# 3.net
KiCad netlist of a schematic drawn in Altium Designer
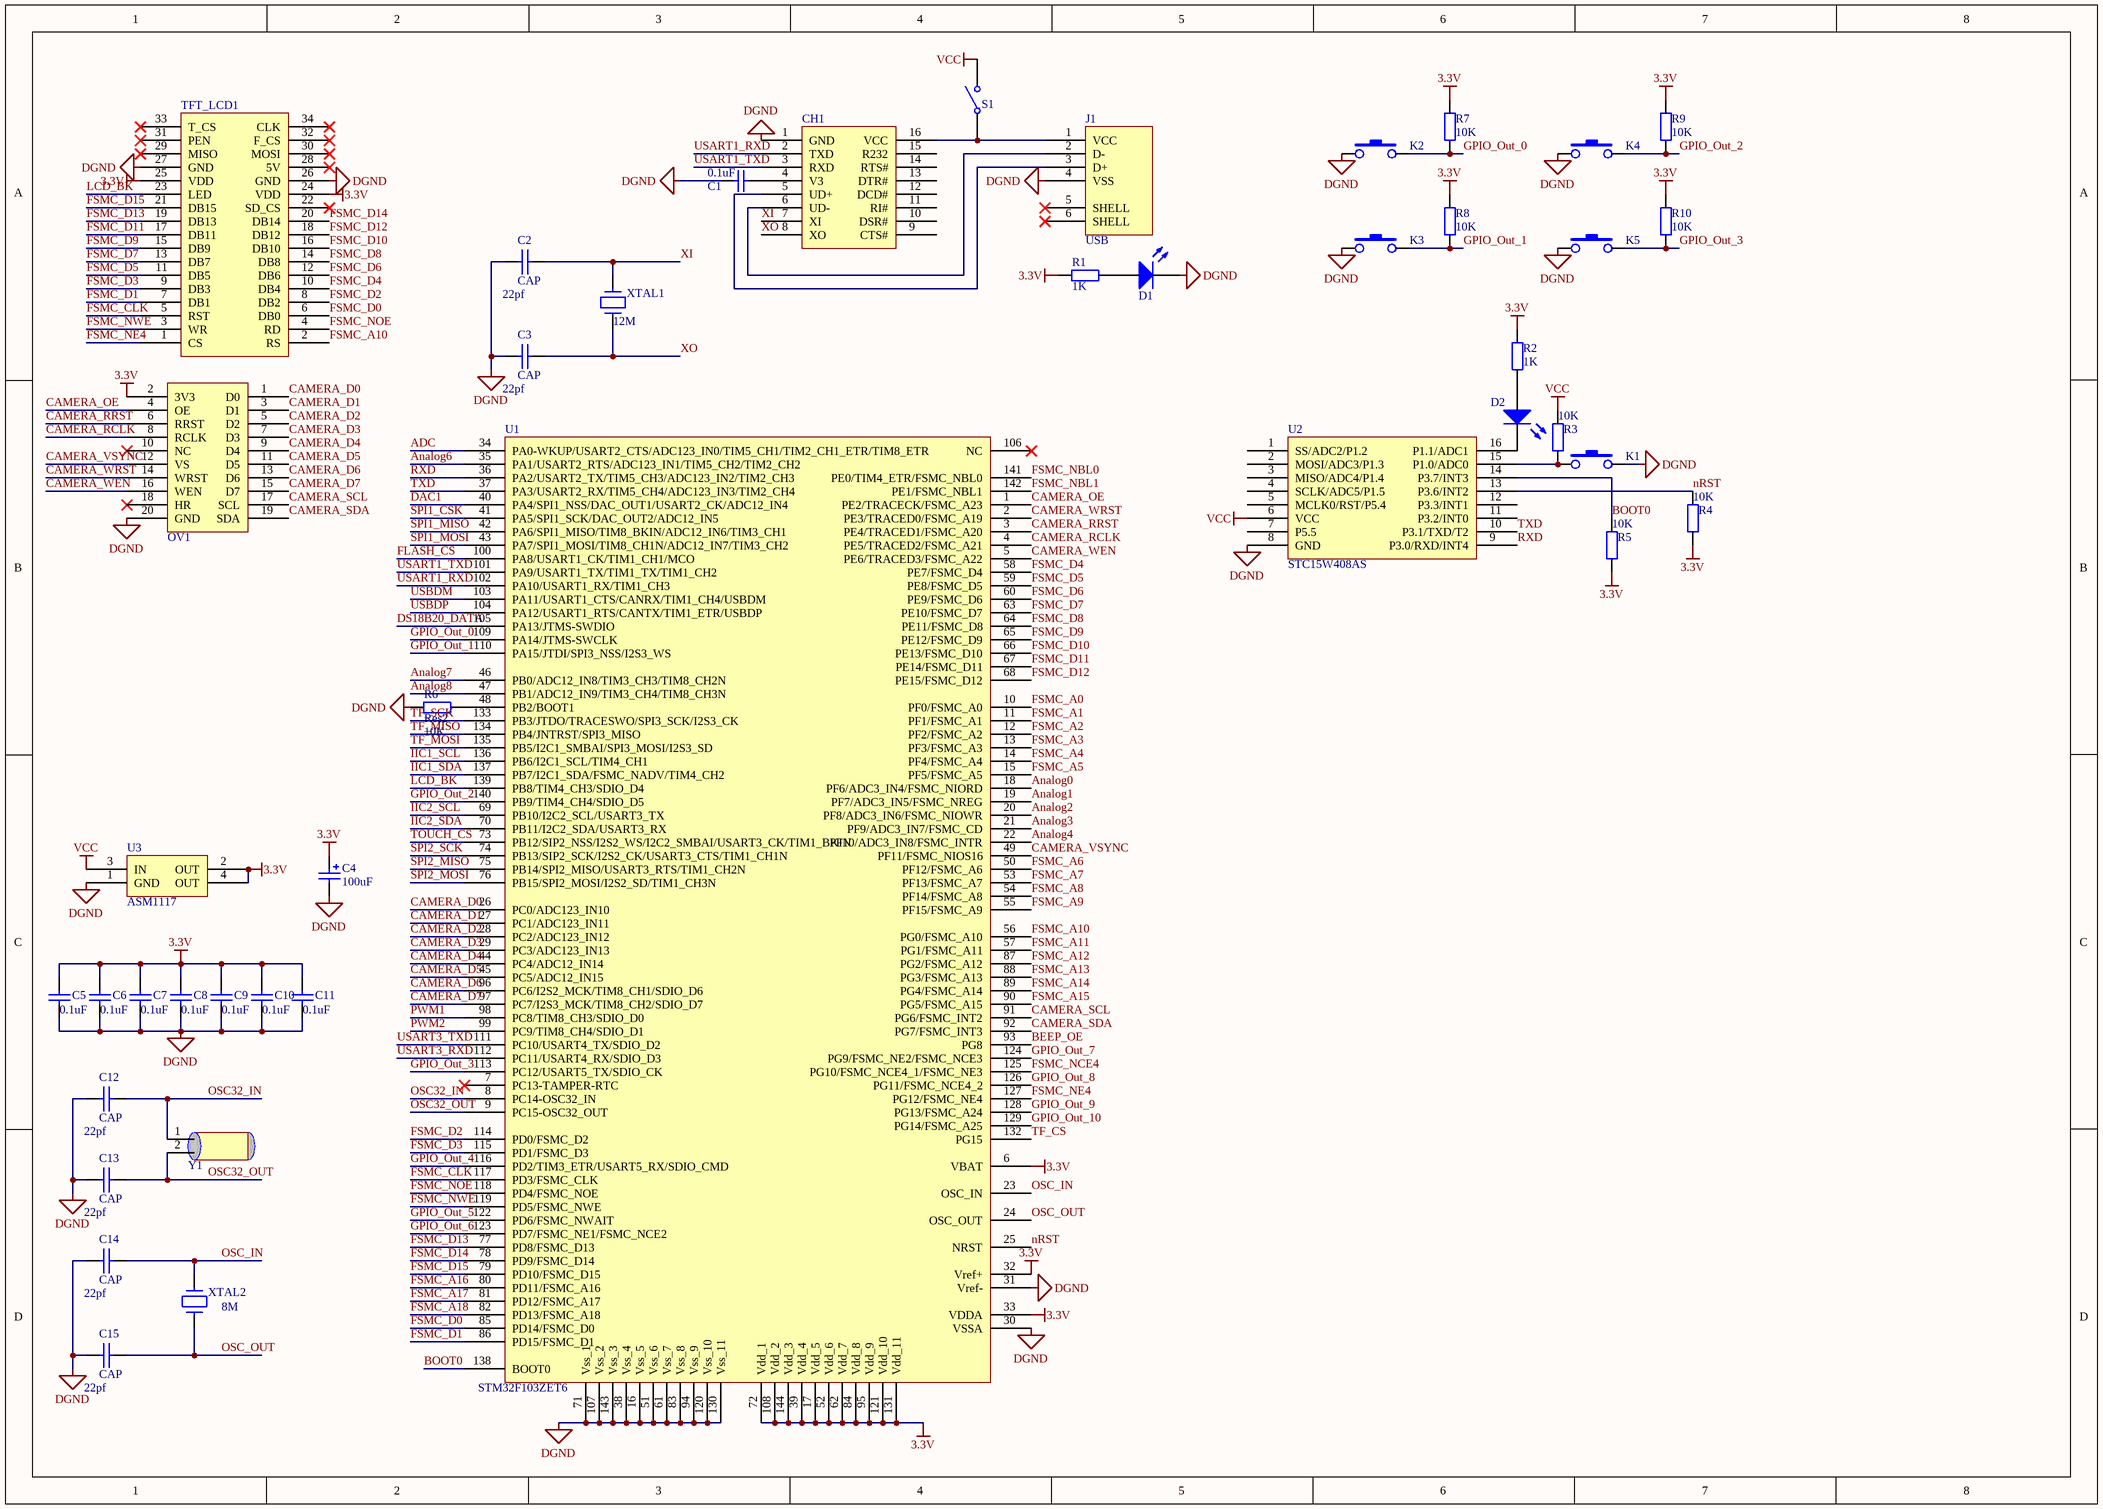
[diagram p0: 测试板3.SchDoc]

(export (version "E")
  (design (tool "Eeschema 10.0.6"))
  (components
    (comp (ref "C1")
      (value "0.1uF")
      (footprint "0805")
      (description "Capacitor")
      (fields (field (name "Comment") "Cap") (field (name "PUBLISHER") "Altium Limited"))
      (libsource (lib "Miscellaneous Devices") (part "Cap"))
    )
    (comp (ref "C2")
      (value "CAP")
      (footprint "0805")
      (fields (field (name "ALTIUM_VALUE") "22pf"))
      (libsource (lib "常用元件库") (part "CAP"))
    )
    (comp (ref "C3")
      (value "CAP")
      (footprint "0805")
      (fields (field (name "ALTIUM_VALUE") "22pf"))
      (libsource (lib "常用元件库") (part "CAP"))
    )
    (comp (ref "C4")
      (value "100uF")
      (footprint "RB.1/.3")
      (description "Polarized Capacitor (Axial)")
      (fields (field (name "Comment") "Cap Pol2") (field (name "PUBLISHER") "Altium Limited"))
      (libsource (lib "Miscellaneous Devices") (part "Cap Pol2"))
    )
    (comp (ref "C5")
      (value "0.1uF")
      (footprint "0805")
      (description "Capacitor")
      (fields (field (name "Comment") "Cap") (field (name "PUBLISHER") "Altium Limited"))
      (libsource (lib "Miscellaneous Devices") (part "Cap"))
    )
    (comp (ref "C6")
      (value "0.1uF")
      (footprint "0805")
      (description "Capacitor")
      (fields (field (name "Comment") "Cap") (field (name "PUBLISHER") "Altium Limited"))
      (libsource (lib "Miscellaneous Devices") (part "Cap"))
    )
    (comp (ref "C7")
      (value "0.1uF")
      (footprint "0805")
      (description "Capacitor")
      (fields (field (name "Comment") "Cap") (field (name "PUBLISHER") "Altium Limited"))
      (libsource (lib "Miscellaneous Devices") (part "Cap"))
    )
    (comp (ref "C8")
      (value "0.1uF")
      (footprint "0805")
      (description "Capacitor")
      (fields (field (name "Comment") "Cap") (field (name "PUBLISHER") "Altium Limited"))
      (libsource (lib "Miscellaneous Devices") (part "Cap"))
    )
    (comp (ref "C9")
      (value "0.1uF")
      (footprint "0805")
      (description "Capacitor")
      (fields (field (name "Comment") "Cap") (field (name "PUBLISHER") "Altium Limited"))
      (libsource (lib "Miscellaneous Devices") (part "Cap"))
    )
    (comp (ref "C10")
      (value "0.1uF")
      (footprint "0805")
      (description "Capacitor")
      (fields (field (name "Comment") "Cap") (field (name "PUBLISHER") "Altium Limited"))
      (libsource (lib "Miscellaneous Devices") (part "Cap"))
    )
    (comp (ref "C11")
      (value "0.1uF")
      (footprint "0805")
      (description "Capacitor")
      (fields (field (name "Comment") "Cap") (field (name "PUBLISHER") "Altium Limited"))
      (libsource (lib "Miscellaneous Devices") (part "Cap"))
    )
    (comp (ref "C12")
      (value "CAP")
      (footprint "0805")
      (fields (field (name "ALTIUM_VALUE") "22pf"))
      (libsource (lib "常用元件库") (part "CAP"))
    )
    (comp (ref "C13")
      (value "CAP")
      (footprint "0805")
      (fields (field (name "ALTIUM_VALUE") "22pf"))
      (libsource (lib "常用元件库") (part "CAP"))
    )
    (comp (ref "C14")
      (value "CAP")
      (footprint "0805")
      (fields (field (name "ALTIUM_VALUE") "22pf"))
      (libsource (lib "常用元件库") (part "CAP"))
    )
    (comp (ref "C15")
      (value "CAP")
      (footprint "0805")
      (fields (field (name "ALTIUM_VALUE") "22pf"))
      (libsource (lib "常用元件库") (part "CAP"))
    )
    (comp (ref "CH1")
      (value "Component_1")
      (footprint "SOIC127P600X170-16N")
      (libsource (lib "CH340G") (part "Component_1"))
    )
    (comp (ref "D1")
      (value "LED0")
      (footprint "LED-0805")
      (description "发光二极管")
      (fields (field (name "PUBLISHER") "Altium Limited"))
      (libsource (lib "fszhang") (part "LED0"))
    )
    (comp (ref "D2")
      (value "LED0")
      (footprint "LED-0805")
      (description "发光二极管")
      (fields (field (name "PUBLISHER") "Altium Limited"))
      (libsource (lib "fszhang") (part "LED0"))
    )
    (comp (ref "J1")
      (value "USB")
      (footprint "USB_B1")
      (description "USB接口")
      (libsource (lib "HDR_fszhang") (part "USB"))
    )
    (comp (ref "K1") (value "button") (footprint "SW_PB4_A1") (libsource (lib "my Library") (part "button")))
    (comp (ref "K2") (value "button") (footprint "SW_PB4_A1") (libsource (lib "my Library") (part "button")))
    (comp (ref "K3") (value "button") (footprint "SW_PB4_A1") (libsource (lib "my Library") (part "button")))
    (comp (ref "K4") (value "button") (footprint "SW_PB4_A1") (libsource (lib "my Library") (part "button")))
    (comp (ref "K5") (value "button") (footprint "SW_PB4_A1") (libsource (lib "my Library") (part "button")))
    (comp (ref "OV1")
      (value "OV7725摄像头")
      (footprint "HDR2X10")
      (libsource (lib "显示屏及摄像头") (part "OV7725摄像头"))
    )
    (comp (ref "R1")
      (value "1K")
      (footprint "0805")
      (description "Resistor")
      (fields (field (name "Comment") "Res2") (field (name "PUBLISHER") "Altium Limited"))
      (libsource (lib "") (part "Res2_2"))
    )
    (comp (ref "R2")
      (value "1K")
      (footprint "0805")
      (description "Resistor")
      (fields (field (name "Comment") "Res2") (field (name "PUBLISHER") "Altium Limited"))
      (libsource (lib "") (part "Res2_1"))
    )
    (comp (ref "R3")
      (value "10K")
      (footprint "0805")
      (description "Resistor")
      (fields (field (name "Comment") "Res2") (field (name "PUBLISHER") "Altium Limited"))
      (libsource (lib "Miscellaneous Devices") (part "Res2"))
    )
    (comp (ref "R4")
      (value "10K")
      (footprint "0805")
      (description "Resistor")
      (fields (field (name "Comment") "Res2") (field (name "PUBLISHER") "Altium Limited"))
      (libsource (lib "Miscellaneous Devices") (part "Res2"))
    )
    (comp (ref "R5")
      (value "10K")
      (footprint "0805")
      (description "Resistor")
      (fields (field (name "Comment") "Res2") (field (name "PUBLISHER") "Altium Limited"))
      (libsource (lib "Miscellaneous Devices") (part "Res2"))
    )
    (comp (ref "R6")
      (value "Res2")
      (footprint "0805")
      (description "Resistor")
      (fields (field (name "ALTIUM_VALUE") "10K") (field (name "PUBLISHER") "Altium Limited"))
      (libsource (lib "") (part "Res2_2"))
    )
    (comp (ref "R7")
      (value "10K")
      (footprint "0805")
      (description "Resistor")
      (fields (field (name "Comment") "Res2") (field (name "PUBLISHER") "Altium Limited"))
      (libsource (lib "") (part "Res2_1"))
    )
    (comp (ref "R8")
      (value "10K")
      (footprint "0805")
      (description "Resistor")
      (fields (field (name "Comment") "Res2") (field (name "PUBLISHER") "Altium Limited"))
      (libsource (lib "") (part "Res2_1"))
    )
    (comp (ref "R9")
      (value "10K")
      (footprint "0805")
      (description "Resistor")
      (fields (field (name "Comment") "Res2") (field (name "PUBLISHER") "Altium Limited"))
      (libsource (lib "") (part "Res2_1"))
    )
    (comp (ref "R10")
      (value "10K")
      (footprint "0805")
      (description "Resistor")
      (fields (field (name "Comment") "Res2") (field (name "PUBLISHER") "Altium Limited"))
      (libsource (lib "") (part "Res2_1"))
    )
    (comp (ref "S1")
      (value "SW-SPST")
      (footprint "SWITCH_B1")
      (description "Single-Pole, Single-Throw Switch")
      (fields (field (name "PUBLISHER") "Altium Limited"))
      (libsource (lib "Miscellaneous Devices") (part "SW-SPST"))
    )
    (comp (ref "TFT_LCD1")
      (value "Component_1")
      (footprint "HDR2X17")
      (libsource (lib "显示屏") (part "Component_1"))
    )
    (comp (ref "U1")
      (value "STM32F103ZET6")
      (footprint "TQFP-144")
      (libsource (lib "STM32F103ZET6") (part "STM32F103ZET6"))
    )
    (comp (ref "U2")
      (value "STC15W408AS")
      (footprint "SOIC127P600X170-16N")
      (libsource (lib "显示屏及摄像头") (part "STC15W408AS"))
    )
    (comp (ref "U3")
      (value "ASM1117")
      (footprint "SOT223")
      (description "3.3V稳压芯片")
      (libsource (lib "fszhang") (part "ASM1117"))
    )
    (comp (ref "XTAL1")
      (value "12M")
      (footprint "X-SM49")
      (fields (field (name "Comment") "CRYSTAL"))
      (libsource (lib "常用元件库") (part "CRYSTAL"))
    )
    (comp (ref "XTAL2")
      (value "8M")
      (footprint "X-SM49")
      (fields (field (name "Comment") "CRYSTAL"))
      (libsource (lib "常用元件库") (part "CRYSTAL"))
    )
    (comp (ref "Y1") (value "32K晶振") (footprint "X-TC15") (libsource (lib "Library 1") (part "32K晶振")))
  )
  (nets
    (net (code "1") (name "/ADC") (class "Default")
      (node (ref "U1") (pin "34") (pinfunction "PA0-WKUP/USART2_CTS/ADC123_IN0/TIM5_CH1/TIM2_CH1_ETR/TIM8_ETR_34") (pintype "passive"))
    )
    (net (code "2") (name "/Analog0") (class "Default")
      (node (ref "U1") (pin "18") (pinfunction "PF6/ADC3_IN4/FSMC_NIORD_18") (pintype "passive"))
    )
    (net (code "3") (name "/Analog1") (class "Default")
      (node (ref "U1") (pin "19") (pinfunction "PF7/ADC3_IN5/FSMC_NREG_19") (pintype "passive"))
    )
    (net (code "4") (name "/Analog2") (class "Default")
      (node (ref "U1") (pin "20") (pinfunction "PF8/ADC3_IN6/FSMC_NIOWR_20") (pintype "passive"))
    )
    (net (code "5") (name "/Analog3") (class "Default")
      (node (ref "U1") (pin "21") (pinfunction "PF9/ADC3_IN7/FSMC_CD_21") (pintype "passive"))
    )
    (net (code "6") (name "/Analog4") (class "Default")
      (node (ref "U1") (pin "22") (pinfunction "PF10/ADC3_IN8/FSMC_INTR_22") (pintype "passive"))
    )
    (net (code "7") (name "/Analog6") (class "Default")
      (node (ref "U1") (pin "35") (pinfunction "PA1/USART2_RTS/ADC123_IN1/TIM5_CH2/TIM2_CH2_35") (pintype "passive"))
    )
    (net (code "8") (name "/Analog7") (class "Default")
      (node (ref "U1") (pin "46") (pinfunction "PB0/ADC12_IN8/TIM3_CH3/TIM8_CH2N_46") (pintype "passive"))
    )
    (net (code "9") (name "/Analog8") (class "Default")
      (node (ref "U1") (pin "47") (pinfunction "PB1/ADC12_IN9/TIM3_CH4/TIM8_CH3N_47") (pintype "passive"))
    )
    (net (code "10") (name "/BEEP_OE") (class "Default")
      (node (ref "U1") (pin "93") (pinfunction "PG8_93") (pintype "passive"))
    )
    (net (code "11") (name "/BOOT0") (class "Default")
      (node (ref "R5") (pin "2") (pinfunction "2_2") (pintype "passive"))
      (node (ref "U1") (pin "138") (pinfunction "BOOT0_138") (pintype "passive"))
      (node (ref "U2") (pin "14") (pinfunction "P3.7/INT3_14") (pintype "passive"))
    )
    (net (code "12") (name "/CAMERA_D0") (class "Default")
      (node (ref "OV1") (pin "1") (pinfunction "D0_1") (pintype "passive"))
      (node (ref "U1") (pin "26") (pinfunction "PC0/ADC123_IN10_26") (pintype "passive"))
    )
    (net (code "13") (name "/CAMERA_D1") (class "Default")
      (node (ref "OV1") (pin "3") (pinfunction "D1_3") (pintype "passive"))
      (node (ref "U1") (pin "27") (pinfunction "PC1/ADC123_IN11_27") (pintype "passive"))
    )
    (net (code "14") (name "/CAMERA_D2") (class "Default")
      (node (ref "OV1") (pin "5") (pinfunction "D2_5") (pintype "passive"))
      (node (ref "U1") (pin "28") (pinfunction "PC2/ADC123_IN12_28") (pintype "passive"))
    )
    (net (code "15") (name "/CAMERA_D3") (class "Default")
      (node (ref "OV1") (pin "7") (pinfunction "D3_7") (pintype "passive"))
      (node (ref "U1") (pin "29") (pinfunction "PC3/ADC123_IN13_29") (pintype "passive"))
    )
    (net (code "16") (name "/CAMERA_D4") (class "Default")
      (node (ref "OV1") (pin "9") (pinfunction "D4_9") (pintype "passive"))
      (node (ref "U1") (pin "44") (pinfunction "PC4/ADC12_IN14_44") (pintype "passive"))
    )
    (net (code "17") (name "/CAMERA_D5") (class "Default")
      (node (ref "OV1") (pin "11") (pinfunction "D5_11") (pintype "passive"))
      (node (ref "U1") (pin "45") (pinfunction "PC5/ADC12_IN15_45") (pintype "passive"))
    )
    (net (code "18") (name "/CAMERA_D6") (class "Default")
      (node (ref "OV1") (pin "13") (pinfunction "D6_13") (pintype "passive"))
      (node (ref "U1") (pin "96") (pinfunction "PC6/I2S2_MCK/TIM8_CH1/SDIO_D6_96") (pintype "passive"))
    )
    (net (code "19") (name "/CAMERA_D7") (class "Default")
      (node (ref "OV1") (pin "15") (pinfunction "D7_15") (pintype "passive"))
      (node (ref "U1") (pin "97") (pinfunction "PC7/I2S3_MCK/TIM8_CH2/SDIO_D7_97") (pintype "passive"))
    )
    (net (code "20") (name "/CAMERA_OE") (class "Default")
      (node (ref "OV1") (pin "4") (pinfunction "OE_4") (pintype "passive"))
      (node (ref "U1") (pin "1") (pinfunction "PE2/TRACECK/FSMC_A23_1") (pintype "passive"))
    )
    (net (code "21") (name "/CAMERA_RCLK") (class "Default")
      (node (ref "OV1") (pin "8") (pinfunction "RCLK_8") (pintype "passive"))
      (node (ref "U1") (pin "4") (pinfunction "PE5/TRACED2/FSMC_A21_4") (pintype "passive"))
    )
    (net (code "22") (name "/CAMERA_RRST") (class "Default")
      (node (ref "OV1") (pin "6") (pinfunction "RRST_6") (pintype "passive"))
      (node (ref "U1") (pin "3") (pinfunction "PE4/TRACED1/FSMC_A20_3") (pintype "passive"))
    )
    (net (code "23") (name "/CAMERA_SCL") (class "Default")
      (node (ref "OV1") (pin "17") (pinfunction "SCL_17") (pintype "passive"))
      (node (ref "U1") (pin "91") (pinfunction "PG6/FSMC_INT2_91") (pintype "passive"))
    )
    (net (code "24") (name "/CAMERA_SDA") (class "Default")
      (node (ref "OV1") (pin "19") (pinfunction "SDA_19") (pintype "passive"))
      (node (ref "U1") (pin "92") (pinfunction "PG7/FSMC_INT3_92") (pintype "passive"))
    )
    (net (code "25") (name "/CAMERA_VSYNC") (class "Default")
      (node (ref "OV1") (pin "12") (pinfunction "VS_12") (pintype "passive"))
      (node (ref "U1") (pin "49") (pinfunction "PF11/FSMC_NIOS16_49") (pintype "passive"))
    )
    (net (code "26") (name "/CAMERA_WEN") (class "Default")
      (node (ref "OV1") (pin "16") (pinfunction "WEN_16") (pintype "passive"))
      (node (ref "U1") (pin "5") (pinfunction "PE6/TRACED3/FSMC_A22_5") (pintype "passive"))
    )
    (net (code "27") (name "/CAMERA_WRST") (class "Default")
      (node (ref "OV1") (pin "14") (pinfunction "WRST_14") (pintype "passive"))
      (node (ref "U1") (pin "2") (pinfunction "PE3/TRACED0/FSMC_A19_2") (pintype "passive"))
    )
    (net (code "28") (name "/DAC1") (class "Default")
      (node (ref "U1") (pin "40") (pinfunction "PA4/SPI1_NSS/DAC_OUT1/USART2_CK/ADC12_IN4_40") (pintype "passive"))
    )
    (net (code "29") (name "/DS18B20_DATA") (class "Default")
      (node (ref "U1") (pin "105") (pinfunction "PA13/JTMS-SWDIO_105") (pintype "passive"))
    )
    (net (code "30") (name "/FLASH_CS") (class "Default")
      (node (ref "U1") (pin "100") (pinfunction "PA8/USART1_CK/TIM1_CH1/MCO_100") (pintype "passive"))
    )
    (net (code "31") (name "/FSMC_A0") (class "Default")
      (node (ref "U1") (pin "10") (pinfunction "PF0/FSMC_A0_10") (pintype "passive"))
    )
    (net (code "32") (name "/FSMC_A1") (class "Default")
      (node (ref "U1") (pin "11") (pinfunction "PF1/FSMC_A1_11") (pintype "passive"))
    )
    (net (code "33") (name "/FSMC_A2") (class "Default")
      (node (ref "U1") (pin "12") (pinfunction "PF2/FSMC_A2_12") (pintype "passive"))
    )
    (net (code "34") (name "/FSMC_A3") (class "Default")
      (node (ref "U1") (pin "13") (pinfunction "PF3/FSMC_A3_13") (pintype "passive"))
    )
    (net (code "35") (name "/FSMC_A4") (class "Default")
      (node (ref "U1") (pin "14") (pinfunction "PF4/FSMC_A4_14") (pintype "passive"))
    )
    (net (code "36") (name "/FSMC_A5") (class "Default")
      (node (ref "U1") (pin "15") (pinfunction "PF5/FSMC_A5_15") (pintype "passive"))
    )
    (net (code "37") (name "/FSMC_A6") (class "Default")
      (node (ref "U1") (pin "50") (pinfunction "PF12/FSMC_A6_50") (pintype "passive"))
    )
    (net (code "38") (name "/FSMC_A7") (class "Default")
      (node (ref "U1") (pin "53") (pinfunction "PF13/FSMC_A7_53") (pintype "passive"))
    )
    (net (code "39") (name "/FSMC_A8") (class "Default")
      (node (ref "U1") (pin "54") (pinfunction "PF14/FSMC_A8_54") (pintype "passive"))
    )
    (net (code "40") (name "/FSMC_A9") (class "Default")
      (node (ref "U1") (pin "55") (pinfunction "PF15/FSMC_A9_55") (pintype "passive"))
    )
    (net (code "41") (name "/FSMC_A10") (class "Default")
      (node (ref "TFT_LCD1") (pin "2") (pinfunction "RS_2") (pintype "passive"))
      (node (ref "U1") (pin "56") (pinfunction "PG0/FSMC_A10_56") (pintype "passive"))
    )
    (net (code "42") (name "/FSMC_A11") (class "Default")
      (node (ref "U1") (pin "57") (pinfunction "PG1/FSMC_A11_57") (pintype "passive"))
    )
    (net (code "43") (name "/FSMC_A12") (class "Default")
      (node (ref "U1") (pin "87") (pinfunction "PG2/FSMC_A12_87") (pintype "passive"))
    )
    (net (code "44") (name "/FSMC_A13") (class "Default")
      (node (ref "U1") (pin "88") (pinfunction "PG3/FSMC_A13_88") (pintype "passive"))
    )
    (net (code "45") (name "/FSMC_A14") (class "Default")
      (node (ref "U1") (pin "89") (pinfunction "PG4/FSMC_A14_89") (pintype "passive"))
    )
    (net (code "46") (name "/FSMC_A15") (class "Default")
      (node (ref "U1") (pin "90") (pinfunction "PG5/FSMC_A15_90") (pintype "passive"))
    )
    (net (code "47") (name "/FSMC_A16") (class "Default")
      (node (ref "U1") (pin "80") (pinfunction "PD11/FSMC_A16_80") (pintype "passive"))
    )
    (net (code "48") (name "/FSMC_A17") (class "Default")
      (node (ref "U1") (pin "81") (pinfunction "PD12/FSMC_A17_81") (pintype "passive"))
    )
    (net (code "49") (name "/FSMC_A18") (class "Default")
      (node (ref "U1") (pin "82") (pinfunction "PD13/FSMC_A18_82") (pintype "passive"))
    )
    (net (code "50") (name "/FSMC_CLK") (class "Default")
      (node (ref "TFT_LCD1") (pin "5") (pinfunction "RST_5") (pintype "passive"))
      (node (ref "U1") (pin "117") (pinfunction "PD3/FSMC_CLK_117") (pintype "passive"))
    )
    (net (code "51") (name "/FSMC_D0") (class "Default")
      (node (ref "TFT_LCD1") (pin "6") (pinfunction "DB0_6") (pintype "passive"))
      (node (ref "U1") (pin "85") (pinfunction "PD14/FSMC_D0_85") (pintype "passive"))
    )
    (net (code "52") (name "/FSMC_D1") (class "Default")
      (node (ref "TFT_LCD1") (pin "7") (pinfunction "DB1_7") (pintype "passive"))
      (node (ref "U1") (pin "86") (pinfunction "PD15/FSMC_D1_86") (pintype "passive"))
    )
    (net (code "53") (name "/FSMC_D2") (class "Default")
      (node (ref "TFT_LCD1") (pin "8") (pinfunction "DB2_8") (pintype "passive"))
      (node (ref "U1") (pin "114") (pinfunction "PD0/FSMC_D2_114") (pintype "passive"))
    )
    (net (code "54") (name "/FSMC_D3") (class "Default")
      (node (ref "TFT_LCD1") (pin "9") (pinfunction "DB3_9") (pintype "passive"))
      (node (ref "U1") (pin "115") (pinfunction "PD1/FSMC_D3_115") (pintype "passive"))
    )
    (net (code "55") (name "/FSMC_D4") (class "Default")
      (node (ref "TFT_LCD1") (pin "10") (pinfunction "DB4_10") (pintype "passive"))
      (node (ref "U1") (pin "58") (pinfunction "PE7/FSMC_D4_58") (pintype "passive"))
    )
    (net (code "56") (name "/FSMC_D5") (class "Default")
      (node (ref "TFT_LCD1") (pin "11") (pinfunction "DB5_11") (pintype "passive"))
      (node (ref "U1") (pin "59") (pinfunction "PE8/FSMC_D5_59") (pintype "passive"))
    )
    (net (code "57") (name "/FSMC_D6") (class "Default")
      (node (ref "TFT_LCD1") (pin "12") (pinfunction "DB6_12") (pintype "passive"))
      (node (ref "U1") (pin "60") (pinfunction "PE9/FSMC_D6_60") (pintype "passive"))
    )
    (net (code "58") (name "/FSMC_D7") (class "Default")
      (node (ref "TFT_LCD1") (pin "13") (pinfunction "DB7_13") (pintype "passive"))
      (node (ref "U1") (pin "63") (pinfunction "PE10/FSMC_D7_63") (pintype "passive"))
    )
    (net (code "59") (name "/FSMC_D8") (class "Default")
      (node (ref "TFT_LCD1") (pin "14") (pinfunction "DB8_14") (pintype "passive"))
      (node (ref "U1") (pin "64") (pinfunction "PE11/FSMC_D8_64") (pintype "passive"))
    )
    (net (code "60") (name "/FSMC_D9") (class "Default")
      (node (ref "TFT_LCD1") (pin "15") (pinfunction "DB9_15") (pintype "passive"))
      (node (ref "U1") (pin "65") (pinfunction "PE12/FSMC_D9_65") (pintype "passive"))
    )
    (net (code "61") (name "/FSMC_D10") (class "Default")
      (node (ref "TFT_LCD1") (pin "16") (pinfunction "DB10_16") (pintype "passive"))
      (node (ref "U1") (pin "66") (pinfunction "PE13/FSMC_D10_66") (pintype "passive"))
    )
    (net (code "62") (name "/FSMC_D11") (class "Default")
      (node (ref "TFT_LCD1") (pin "17") (pinfunction "DB11_17") (pintype "passive"))
      (node (ref "U1") (pin "67") (pinfunction "PE14/FSMC_D11_67") (pintype "passive"))
    )
    (net (code "63") (name "/FSMC_D12") (class "Default")
      (node (ref "TFT_LCD1") (pin "18") (pinfunction "DB12_18") (pintype "passive"))
      (node (ref "U1") (pin "68") (pinfunction "PE15/FSMC_D12_68") (pintype "passive"))
    )
    (net (code "64") (name "/FSMC_D13") (class "Default")
      (node (ref "TFT_LCD1") (pin "19") (pinfunction "DB13_19") (pintype "passive"))
      (node (ref "U1") (pin "77") (pinfunction "PD8/FSMC_D13_77") (pintype "passive"))
    )
    (net (code "65") (name "/FSMC_D14") (class "Default")
      (node (ref "TFT_LCD1") (pin "20") (pinfunction "DB14_20") (pintype "passive"))
      (node (ref "U1") (pin "78") (pinfunction "PD9/FSMC_D14_78") (pintype "passive"))
    )
    (net (code "66") (name "/FSMC_D15") (class "Default")
      (node (ref "TFT_LCD1") (pin "21") (pinfunction "DB15_21") (pintype "passive"))
      (node (ref "U1") (pin "79") (pinfunction "PD10/FSMC_D15_79") (pintype "passive"))
    )
    (net (code "67") (name "/FSMC_NBL0") (class "Default")
      (node (ref "U1") (pin "141") (pinfunction "PE0/TIM4_ETR/FSMC_NBL0_141") (pintype "passive"))
    )
    (net (code "68") (name "/FSMC_NBL1") (class "Default")
      (node (ref "U1") (pin "142") (pinfunction "PE1/FSMC_NBL1_142") (pintype "passive"))
    )
    (net (code "69") (name "/FSMC_NCE4") (class "Default")
      (node (ref "U1") (pin "125") (pinfunction "PG10/FSMC_NCE4_1/FSMC_NE3_125") (pintype "passive"))
    )
    (net (code "70") (name "/FSMC_NE4") (class "Default")
      (node (ref "TFT_LCD1") (pin "1") (pinfunction "CS_1") (pintype "passive"))
      (node (ref "U1") (pin "127") (pinfunction "PG12/FSMC_NE4_127") (pintype "passive"))
    )
    (net (code "71") (name "/FSMC_NOE") (class "Default")
      (node (ref "TFT_LCD1") (pin "4") (pinfunction "RD_4") (pintype "passive"))
      (node (ref "U1") (pin "118") (pinfunction "PD4/FSMC_NOE_118") (pintype "passive"))
    )
    (net (code "72") (name "/FSMC_NWE") (class "Default")
      (node (ref "TFT_LCD1") (pin "3") (pinfunction "WR_3") (pintype "passive"))
      (node (ref "U1") (pin "119") (pinfunction "PD5/FSMC_NWE_119") (pintype "passive"))
    )
    (net (code "73") (name "/GPIO_Out_0") (class "Default")
      (node (ref "K2") (pin "2") (pinfunction "2_2") (pintype "passive"))
      (node (ref "R7") (pin "2") (pinfunction "2_2") (pintype "passive"))
      (node (ref "U1") (pin "109") (pinfunction "PA14/JTMS-SWCLK_109") (pintype "passive"))
    )
    (net (code "74") (name "/GPIO_Out_1") (class "Default")
      (node (ref "K3") (pin "2") (pinfunction "2_2") (pintype "passive"))
      (node (ref "R8") (pin "2") (pinfunction "2_2") (pintype "passive"))
      (node (ref "U1") (pin "110") (pinfunction "PA15/JTDI/SPI3_NSS/I2S3_WS_110") (pintype "passive"))
    )
    (net (code "75") (name "/GPIO_Out_2") (class "Default")
      (node (ref "K4") (pin "2") (pinfunction "2_2") (pintype "passive"))
      (node (ref "R9") (pin "2") (pinfunction "2_2") (pintype "passive"))
      (node (ref "U1") (pin "140") (pinfunction "PB9/TIM4_CH4/SDIO_D5_140") (pintype "passive"))
    )
    (net (code "76") (name "/GPIO_Out_3") (class "Default")
      (node (ref "K5") (pin "2") (pinfunction "2_2") (pintype "passive"))
      (node (ref "R10") (pin "2") (pinfunction "2_2") (pintype "passive"))
      (node (ref "U1") (pin "113") (pinfunction "PC12/USART5_TX/SDIO_CK_113") (pintype "passive"))
    )
    (net (code "77") (name "/GPIO_Out_4") (class "Default")
      (node (ref "U1") (pin "116") (pinfunction "PD2/TIM3_ETR/USART5_RX/SDIO_CMD_116") (pintype "passive"))
    )
    (net (code "78") (name "/GPIO_Out_5") (class "Default")
      (node (ref "U1") (pin "122") (pinfunction "PD6/FSMC_NWAIT_122") (pintype "passive"))
    )
    (net (code "79") (name "/GPIO_Out_6") (class "Default")
      (node (ref "U1") (pin "123") (pinfunction "PD7/FSMC_NE1/FSMC_NCE2_123") (pintype "passive"))
    )
    (net (code "80") (name "/GPIO_Out_7") (class "Default")
      (node (ref "U1") (pin "124") (pinfunction "PG9/FSMC_NE2/FSMC_NCE3_124") (pintype "passive"))
    )
    (net (code "81") (name "/GPIO_Out_8") (class "Default")
      (node (ref "U1") (pin "126") (pinfunction "PG11/FSMC_NCE4_2_126") (pintype "passive"))
    )
    (net (code "82") (name "/GPIO_Out_9") (class "Default")
      (node (ref "U1") (pin "128") (pinfunction "PG13/FSMC_A24_128") (pintype "passive"))
    )
    (net (code "83") (name "/GPIO_Out_10") (class "Default")
      (node (ref "U1") (pin "129") (pinfunction "PG14/FSMC_A25_129") (pintype "passive"))
    )
    (net (code "84") (name "/IIC1_SCL") (class "Default")
      (node (ref "U1") (pin "136") (pinfunction "PB6/I2C1_SCL/TIM4_CH1_136") (pintype "passive"))
    )
    (net (code "85") (name "/IIC1_SDA") (class "Default")
      (node (ref "U1") (pin "137") (pinfunction "PB7/I2C1_SDA/FSMC_NADV/TIM4_CH2_137") (pintype "passive"))
    )
    (net (code "86") (name "/IIC2_SCL") (class "Default")
      (node (ref "U1") (pin "69") (pinfunction "PB10/I2C2_SCL/USART3_TX_69") (pintype "passive"))
    )
    (net (code "87") (name "/IIC2_SDA") (class "Default")
      (node (ref "U1") (pin "70") (pinfunction "PB11/I2C2_SDA/USART3_RX_70") (pintype "passive"))
    )
    (net (code "88") (name "/LCD_BK") (class "Default")
      (node (ref "TFT_LCD1") (pin "23") (pinfunction "LED_23") (pintype "passive"))
      (node (ref "U1") (pin "139") (pinfunction "PB8/TIM4_CH3/SDIO_D4_139") (pintype "passive"))
    )
    (net (code "89") (name "/OSC32_IN") (class "Default")
      (node (ref "C12") (pin "2") (pinfunction "2_2") (pintype "passive"))
      (node (ref "U1") (pin "8") (pinfunction "PC14-OSC32_IN_8") (pintype "passive"))
      (node (ref "Y1") (pin "1") (pinfunction "X1_1") (pintype "passive"))
    )
    (net (code "90") (name "/OSC32_OUT") (class "Default")
      (node (ref "C13") (pin "2") (pinfunction "2_2") (pintype "passive"))
      (node (ref "U1") (pin "9") (pinfunction "PC15-OSC32_OUT_9") (pintype "passive"))
      (node (ref "Y1") (pin "2") (pinfunction "X2_2") (pintype "passive"))
    )
    (net (code "91") (name "/OSC_IN") (class "Default")
      (node (ref "C14") (pin "2") (pinfunction "2_2") (pintype "passive"))
      (node (ref "U1") (pin "23") (pinfunction "OSC_IN_23") (pintype "passive"))
      (node (ref "XTAL2") (pin "2") (pinfunction "2_2") (pintype "passive"))
    )
    (net (code "92") (name "/OSC_OUT") (class "Default")
      (node (ref "C15") (pin "2") (pinfunction "2_2") (pintype "passive"))
      (node (ref "U1") (pin "24") (pinfunction "OSC_OUT_24") (pintype "passive"))
      (node (ref "XTAL2") (pin "1") (pinfunction "1_1") (pintype "passive"))
    )
    (net (code "93") (name "/PWM1") (class "Default")
      (node (ref "U1") (pin "98") (pinfunction "PC8/TIM8_CH3/SDIO_D0_98") (pintype "passive"))
    )
    (net (code "94") (name "/PWM2") (class "Default")
      (node (ref "U1") (pin "99") (pinfunction "PC9/TIM8_CH4/SDIO_D1_99") (pintype "passive"))
    )
    (net (code "95") (name "/RXD") (class "Default")
      (node (ref "U1") (pin "36") (pinfunction "PA2/USART2_TX/TIM5_CH3/ADC123_IN2/TIM2_CH3_36") (pintype "passive"))
      (node (ref "U2") (pin "9") (pinfunction "P3.0/RXD/INT4_9") (pintype "passive"))
    )
    (net (code "96") (name "/SPI1_CSK") (class "Default")
      (node (ref "U1") (pin "41") (pinfunction "PA5/SPI1_SCK/DAC_OUT2/ADC12_IN5_41") (pintype "passive"))
    )
    (net (code "97") (name "/SPI1_MISO") (class "Default")
      (node (ref "U1") (pin "42") (pinfunction "PA6/SPI1_MISO/TIM8_BKIN/ADC12_IN6/TIM3_CH1_42") (pintype "passive"))
    )
    (net (code "98") (name "/SPI1_MOSI") (class "Default")
      (node (ref "U1") (pin "43") (pinfunction "PA7/SPI1_MOSI/TIM8_CH1N/ADC12_IN7/TIM3_CH2_43") (pintype "passive"))
    )
    (net (code "99") (name "/SPI2_MISO") (class "Default")
      (node (ref "U1") (pin "75") (pinfunction "PB14/SPI2_MISO/USART3_RTS/TIM1_CH2N_75") (pintype "passive"))
    )
    (net (code "100") (name "/SPI2_MOSI") (class "Default")
      (node (ref "U1") (pin "76") (pinfunction "PB15/SPI2_MOSI/I2S2_SD/TIM1_CH3N_76") (pintype "passive"))
    )
    (net (code "101") (name "/SPI2_SCK") (class "Default")
      (node (ref "U1") (pin "74") (pinfunction "PB13/SIP2_SCK/I2S2_CK/USART3_CTS/TIM1_CH1N_74") (pintype "passive"))
    )
    (net (code "102") (name "/TF_CS") (class "Default")
      (node (ref "U1") (pin "132") (pinfunction "PG15_132") (pintype "passive"))
    )
    (net (code "103") (name "/TF_MISO") (class "Default")
      (node (ref "U1") (pin "134") (pinfunction "PB4/JNTRST/SPI3_MISO_134") (pintype "passive"))
    )
    (net (code "104") (name "/TF_MOSI") (class "Default")
      (node (ref "U1") (pin "135") (pinfunction "PB5/I2C1_SMBAI/SPI3_MOSI/I2S3_SD_135") (pintype "passive"))
    )
    (net (code "105") (name "/TF_SCK") (class "Default")
      (node (ref "U1") (pin "133") (pinfunction "PB3/JTDO/TRACESWO/SPI3_SCK/I2S3_CK_133") (pintype "passive"))
    )
    (net (code "106") (name "/TOUCH_CS") (class "Default")
      (node (ref "U1") (pin "73") (pinfunction "PB12/SIP2_NSS/I2S2_WS/I2C2_SMBAI/USART3_CK/TIM1_BKIN_73") (pintype "passive"))
    )
    (net (code "107") (name "/TXD") (class "Default")
      (node (ref "U1") (pin "37") (pinfunction "PA3/USART2_RX/TIM5_CH4/ADC123_IN3/TIM2_CH4_37") (pintype "passive"))
      (node (ref "U2") (pin "10") (pinfunction "P3.1/TXD/T2_10") (pintype "passive"))
    )
    (net (code "108") (name "/USART1_RXD") (class "Default")
      (node (ref "CH1") (pin "2") (pinfunction "TXD_2") (pintype "passive"))
      (node (ref "U1") (pin "102") (pinfunction "PA10/USART1_RX/TIM1_CH3_102") (pintype "passive"))
    )
    (net (code "109") (name "/USART1_TXD") (class "Default")
      (node (ref "CH1") (pin "3") (pinfunction "RXD_3") (pintype "passive"))
      (node (ref "U1") (pin "101") (pinfunction "PA9/USART1_TX/TIM1_TX/TIM1_CH2_101") (pintype "passive"))
    )
    (net (code "110") (name "/USART3_RXD") (class "Default")
      (node (ref "U1") (pin "112") (pinfunction "PC11/USART4_RX/SDIO_D3_112") (pintype "passive"))
    )
    (net (code "111") (name "/USART3_TXD") (class "Default")
      (node (ref "U1") (pin "111") (pinfunction "PC10/USART4_TX/SDIO_D2_111") (pintype "passive"))
    )
    (net (code "112") (name "/USBDM") (class "Default")
      (node (ref "U1") (pin "103") (pinfunction "PA11/USART1_CTS/CANRX/TIM1_CH4/USBDM_103") (pintype "passive"))
    )
    (net (code "113") (name "/USBDP") (class "Default")
      (node (ref "U1") (pin "104") (pinfunction "PA12/USART1_RTS/CANTX/TIM1_ETR/USBDP_104") (pintype "passive"))
    )
    (net (code "114") (name "/XI") (class "Default")
      (node (ref "C2") (pin "2") (pinfunction "2_2") (pintype "passive"))
      (node (ref "CH1") (pin "7") (pinfunction "XI_7") (pintype "passive"))
      (node (ref "XTAL1") (pin "2") (pinfunction "2_2") (pintype "passive"))
    )
    (net (code "115") (name "/XO") (class "Default")
      (node (ref "C3") (pin "2") (pinfunction "2_2") (pintype "passive"))
      (node (ref "CH1") (pin "8") (pinfunction "XO_8") (pintype "passive"))
      (node (ref "XTAL1") (pin "1") (pinfunction "1_1") (pintype "passive"))
    )
    (net (code "116") (name "/nRST") (class "Default")
      (node (ref "R4") (pin "2") (pinfunction "2_2") (pintype "passive"))
      (node (ref "U1") (pin "25") (pinfunction "NRST_25") (pintype "passive"))
      (node (ref "U2") (pin "13") (pinfunction "P3.6/INT2_13") (pintype "passive"))
    )
    (net (code "117") (name "3.3V") (class "Default")
      (node (ref "C10") (pin "2") (pinfunction "2_2") (pintype "passive"))
      (node (ref "C11") (pin "2") (pinfunction "2_2") (pintype "passive"))
      (node (ref "C4") (pin "1") (pinfunction "1_1") (pintype "passive"))
      (node (ref "C5") (pin "2") (pinfunction "2_2") (pintype "passive"))
      (node (ref "C6") (pin "2") (pinfunction "2_2") (pintype "passive"))
      (node (ref "C7") (pin "2") (pinfunction "2_2") (pintype "passive"))
      (node (ref "C8") (pin "2") (pinfunction "2_2") (pintype "passive"))
      (node (ref "C9") (pin "2") (pinfunction "2_2") (pintype "passive"))
      (node (ref "OV1") (pin "2") (pinfunction "3V3_2") (pintype "passive"))
      (node (ref "R1") (pin "1") (pinfunction "1_1") (pintype "passive"))
      (node (ref "R10") (pin "1") (pinfunction "1_1") (pintype "passive"))
      (node (ref "R2") (pin "1") (pinfunction "1_1") (pintype "passive"))
      (node (ref "R4") (pin "1") (pinfunction "1_1") (pintype "passive"))
      (node (ref "R5") (pin "1") (pinfunction "1_1") (pintype "passive"))
      (node (ref "R7") (pin "1") (pinfunction "1_1") (pintype "passive"))
      (node (ref "R8") (pin "1") (pinfunction "1_1") (pintype "passive"))
      (node (ref "R9") (pin "1") (pinfunction "1_1") (pintype "passive"))
      (node (ref "TFT_LCD1") (pin "24") (pinfunction "VDD_24") (pintype "passive"))
      (node (ref "TFT_LCD1") (pin "25") (pinfunction "VDD_25") (pintype "passive"))
      (node (ref "U1") (pin "108") (pinfunction "Vdd_2_108") (pintype "passive"))
      (node (ref "U1") (pin "121") (pinfunction "Vdd_10_121") (pintype "passive"))
      (node (ref "U1") (pin "131") (pinfunction "Vdd_11_131") (pintype "passive"))
      (node (ref "U1") (pin "144") (pinfunction "Vdd_3_144") (pintype "passive"))
      (node (ref "U1") (pin "17") (pinfunction "Vdd_5_17") (pintype "passive"))
      (node (ref "U1") (pin "32") (pinfunction "Vref+_32") (pintype "passive"))
      (node (ref "U1") (pin "33") (pinfunction "VDDA_33") (pintype "passive"))
      (node (ref "U1") (pin "39") (pinfunction "Vdd_4_39") (pintype "passive"))
      (node (ref "U1") (pin "52") (pinfunction "Vdd_6_52") (pintype "passive"))
      (node (ref "U1") (pin "6") (pinfunction "VBAT_6") (pintype "passive"))
      (node (ref "U1") (pin "62") (pinfunction "Vdd_7_62") (pintype "passive"))
      (node (ref "U1") (pin "72") (pinfunction "Vdd_1_72") (pintype "passive"))
      (node (ref "U1") (pin "84") (pinfunction "Vdd_8_84") (pintype "passive"))
      (node (ref "U1") (pin "95") (pinfunction "Vdd_9_95") (pintype "passive"))
      (node (ref "U3") (pin "2") (pinfunction "OUT_2") (pintype "passive"))
      (node (ref "U3") (pin "4") (pinfunction "OUT_4") (pintype "passive"))
    )
    (net (code "118") (name "DGND") (class "Default")
      (node (ref "C1") (pin "2") (pinfunction "2_2") (pintype "passive"))
      (node (ref "C10") (pin "1") (pinfunction "1_1") (pintype "passive"))
      (node (ref "C11") (pin "1") (pinfunction "1_1") (pintype "passive"))
      (node (ref "C12") (pin "1") (pinfunction "1_1") (pintype "passive"))
      (node (ref "C13") (pin "1") (pinfunction "1_1") (pintype "passive"))
      (node (ref "C14") (pin "1") (pinfunction "1_1") (pintype "passive"))
      (node (ref "C15") (pin "1") (pinfunction "1_1") (pintype "passive"))
      (node (ref "C2") (pin "1") (pinfunction "1_1") (pintype "passive"))
      (node (ref "C3") (pin "1") (pinfunction "1_1") (pintype "passive"))
      (node (ref "C4") (pin "2") (pinfunction "2_2") (pintype "passive"))
      (node (ref "C5") (pin "1") (pinfunction "1_1") (pintype "passive"))
      (node (ref "C6") (pin "1") (pinfunction "1_1") (pintype "passive"))
      (node (ref "C7") (pin "1") (pinfunction "1_1") (pintype "passive"))
      (node (ref "C8") (pin "1") (pinfunction "1_1") (pintype "passive"))
      (node (ref "C9") (pin "1") (pinfunction "1_1") (pintype "passive"))
      (node (ref "CH1") (pin "1") (pinfunction "GND_1") (pintype "passive"))
      (node (ref "D1") (pin "2") (pinfunction "K_2") (pintype "passive"))
      (node (ref "J1") (pin "4") (pinfunction "VSS_4") (pintype "passive"))
      (node (ref "K1") (pin "2") (pinfunction "2_2") (pintype "passive"))
      (node (ref "K2") (pin "1") (pinfunction "1_1") (pintype "passive"))
      (node (ref "K3") (pin "1") (pinfunction "1_1") (pintype "passive"))
      (node (ref "K4") (pin "1") (pinfunction "1_1") (pintype "passive"))
      (node (ref "K5") (pin "1") (pinfunction "1_1") (pintype "passive"))
      (node (ref "OV1") (pin "20") (pinfunction "GND_20") (pintype "passive"))
      (node (ref "R6") (pin "1") (pinfunction "1_1") (pintype "passive"))
      (node (ref "TFT_LCD1") (pin "26") (pinfunction "GND_26") (pintype "passive"))
      (node (ref "TFT_LCD1") (pin "27") (pinfunction "GND_27") (pintype "passive"))
      (node (ref "U1") (pin "107") (pinfunction "Vss_2_107") (pintype "passive"))
      (node (ref "U1") (pin "120") (pinfunction "Vss_10_120") (pintype "passive"))
      (node (ref "U1") (pin "130") (pinfunction "Vss_11_130") (pintype "passive"))
      (node (ref "U1") (pin "143") (pinfunction "Vss_3_143") (pintype "passive"))
      (node (ref "U1") (pin "16") (pinfunction "Vss_5_16") (pintype "passive"))
      (node (ref "U1") (pin "30") (pinfunction "VSSA_30") (pintype "passive"))
      (node (ref "U1") (pin "31") (pinfunction "Vref-_31") (pintype "passive"))
      (node (ref "U1") (pin "38") (pinfunction "Vss_4_38") (pintype "passive"))
      (node (ref "U1") (pin "51") (pinfunction "Vss_6_51") (pintype "passive"))
      (node (ref "U1") (pin "61") (pinfunction "Vss_7_61") (pintype "passive"))
      (node (ref "U1") (pin "71") (pinfunction "Vss_1_71") (pintype "passive"))
      (node (ref "U1") (pin "83") (pinfunction "Vss_8_83") (pintype "passive"))
      (node (ref "U1") (pin "94") (pinfunction "Vss_9_94") (pintype "passive"))
      (node (ref "U2") (pin "8") (pinfunction "GND_8") (pintype "passive"))
      (node (ref "U3") (pin "1") (pinfunction "GND_1") (pintype "passive"))
    )
    (net (code "119") (name "Net-(CH1-UD+)") (class "Default")
      (node (ref "CH1") (pin "5") (pinfunction "UD+_5") (pintype "passive"))
      (node (ref "J1") (pin "3") (pinfunction "D+_3") (pintype "passive"))
    )
    (net (code "120") (name "Net-(CH1-UD-)") (class "Default")
      (node (ref "CH1") (pin "6") (pinfunction "UD-_6") (pintype "passive"))
      (node (ref "J1") (pin "2") (pinfunction "D-_2") (pintype "passive"))
    )
    (net (code "121") (name "Net-(CH1-V3)") (class "Default")
      (node (ref "C1") (pin "1") (pinfunction "1_1") (pintype "passive"))
      (node (ref "CH1") (pin "4") (pinfunction "V3_4") (pintype "passive"))
    )
    (net (code "122") (name "Net-(CH1-VCC)") (class "Default")
      (node (ref "CH1") (pin "16") (pinfunction "VCC_16") (pintype "passive"))
      (node (ref "J1") (pin "1") (pinfunction "VCC_1") (pintype "passive"))
      (node (ref "S1") (pin "1") (pinfunction "COMMON_1") (pintype "passive"))
    )
    (net (code "123") (name "Net-(D1-A)") (class "Default")
      (node (ref "D1") (pin "1") (pinfunction "A_1") (pintype "passive"))
      (node (ref "R1") (pin "2") (pinfunction "2_2") (pintype "passive"))
    )
    (net (code "124") (name "Net-(D2-A)") (class "Default")
      (node (ref "D2") (pin "1") (pinfunction "A_1") (pintype "passive"))
      (node (ref "R2") (pin "2") (pinfunction "2_2") (pintype "passive"))
    )
    (net (code "125") (name "Net-(D2-K)") (class "Default")
      (node (ref "D2") (pin "2") (pinfunction "K_2") (pintype "passive"))
      (node (ref "U2") (pin "16") (pinfunction "P1.1/ADC1_16") (pintype "passive"))
    )
    (net (code "126") (name "Net-(U1-PB2{slash}BOOT1)") (class "Default")
      (node (ref "R6") (pin "2") (pinfunction "2_2") (pintype "passive"))
      (node (ref "U1") (pin "48") (pinfunction "PB2/BOOT1_48") (pintype "passive"))
    )
    (net (code "127") (name "Net-(U2-P1.0{slash}ADC0)") (class "Default")
      (node (ref "K1") (pin "1") (pinfunction "1_1") (pintype "passive"))
      (node (ref "R3") (pin "1") (pinfunction "1_1") (pintype "passive"))
      (node (ref "U2") (pin "15") (pinfunction "P1.0/ADC0_15") (pintype "passive"))
    )
    (net (code "128") (name "VCC") (class "Default")
      (node (ref "R3") (pin "2") (pinfunction "2_2") (pintype "passive"))
      (node (ref "S1") (pin "2") (pinfunction "NO_2") (pintype "passive"))
      (node (ref "U2") (pin "6") (pinfunction "VCC_6") (pintype "passive"))
      (node (ref "U3") (pin "3") (pinfunction "IN_3") (pintype "passive"))
    )
    (net (code "129") (name "unconnected-(CH1-CTS#-Pad9)") (class "Default")
      (node (ref "CH1") (pin "9") (pinfunction "CTS#_9") (pintype "passive"))
    )
    (net (code "130") (name "unconnected-(CH1-DCD#-Pad12)") (class "Default")
      (node (ref "CH1") (pin "12") (pinfunction "DCD#_12") (pintype "passive"))
    )
    (net (code "131") (name "unconnected-(CH1-DSR#-Pad10)") (class "Default")
      (node (ref "CH1") (pin "10") (pinfunction "DSR#_10") (pintype "passive"))
    )
    (net (code "132") (name "unconnected-(CH1-DTR#-Pad13)") (class "Default")
      (node (ref "CH1") (pin "13") (pinfunction "DTR#_13") (pintype "passive"))
    )
    (net (code "133") (name "unconnected-(CH1-R232-Pad15)") (class "Default")
      (node (ref "CH1") (pin "15") (pinfunction "R232_15") (pintype "passive"))
    )
    (net (code "134") (name "unconnected-(CH1-RI#-Pad11)") (class "Default")
      (node (ref "CH1") (pin "11") (pinfunction "RI#_11") (pintype "passive"))
    )
    (net (code "135") (name "unconnected-(CH1-RTS#-Pad14)") (class "Default")
      (node (ref "CH1") (pin "14") (pinfunction "RTS#_14") (pintype "passive"))
    )
    (net (code "136") (name "unconnected-(J1-SHELL-Pad5)") (class "Default")
      (node (ref "J1") (pin "5") (pinfunction "SHELL_5") (pintype "passive+no_connect"))
    )
    (net (code "137") (name "unconnected-(J1-SHELL-Pad6)") (class "Default")
      (node (ref "J1") (pin "6") (pinfunction "SHELL_6") (pintype "passive+no_connect"))
    )
    (net (code "138") (name "unconnected-(OV1-HR-Pad18)") (class "Default")
      (node (ref "OV1") (pin "18") (pinfunction "HR_18") (pintype "passive+no_connect"))
    )
    (net (code "139") (name "unconnected-(OV1-NC-Pad10)") (class "Default")
      (node (ref "OV1") (pin "10") (pinfunction "NC_10") (pintype "passive+no_connect"))
    )
    (net (code "140") (name "unconnected-(TFT_LCD1-5V-Pad28)") (class "Default")
      (node (ref "TFT_LCD1") (pin "28") (pinfunction "5V_28") (pintype "passive+no_connect"))
    )
    (net (code "141") (name "unconnected-(TFT_LCD1-CLK-Pad34)") (class "Default")
      (node (ref "TFT_LCD1") (pin "34") (pinfunction "CLK_34") (pintype "passive+no_connect"))
    )
    (net (code "142") (name "unconnected-(TFT_LCD1-F_CS-Pad32)") (class "Default")
      (node (ref "TFT_LCD1") (pin "32") (pinfunction "F_CS_32") (pintype "passive+no_connect"))
    )
    (net (code "143") (name "unconnected-(TFT_LCD1-MISO-Pad29)") (class "Default")
      (node (ref "TFT_LCD1") (pin "29") (pinfunction "MISO_29") (pintype "passive+no_connect"))
    )
    (net (code "144") (name "unconnected-(TFT_LCD1-MOSI-Pad30)") (class "Default")
      (node (ref "TFT_LCD1") (pin "30") (pinfunction "MOSI_30") (pintype "passive+no_connect"))
    )
    (net (code "145") (name "unconnected-(TFT_LCD1-PEN-Pad31)") (class "Default")
      (node (ref "TFT_LCD1") (pin "31") (pinfunction "PEN_31") (pintype "passive+no_connect"))
    )
    (net (code "146") (name "unconnected-(TFT_LCD1-SD_CS-Pad22)") (class "Default")
      (node (ref "TFT_LCD1") (pin "22") (pinfunction "SD_CS_22") (pintype "passive+no_connect"))
    )
    (net (code "147") (name "unconnected-(TFT_LCD1-T_CS-Pad33)") (class "Default")
      (node (ref "TFT_LCD1") (pin "33") (pinfunction "T_CS_33") (pintype "passive+no_connect"))
    )
    (net (code "148") (name "unconnected-(U1-NC-Pad106)") (class "Default")
      (node (ref "U1") (pin "106") (pinfunction "NC_106") (pintype "passive+no_connect"))
    )
    (net (code "149") (name "unconnected-(U1-PC13-TAMPER-RTC-Pad7)") (class "Default")
      (node (ref "U1") (pin "7") (pinfunction "PC13-TAMPER-RTC_7") (pintype "passive+no_connect"))
    )
    (net (code "150") (name "unconnected-(U2-MCLK0{slash}RST{slash}P5.4-Pad5)") (class "Default")
      (node (ref "U2") (pin "5") (pinfunction "MCLK0/RST/P5.4_5") (pintype "passive"))
    )
    (net (code "151") (name "unconnected-(U2-MISO{slash}ADC4{slash}P1.4-Pad3)") (class "Default")
      (node (ref "U2") (pin "3") (pinfunction "MISO/ADC4/P1.4_3") (pintype "passive"))
    )
    (net (code "152") (name "unconnected-(U2-MOSI{slash}ADC3{slash}P1.3-Pad2)") (class "Default")
      (node (ref "U2") (pin "2") (pinfunction "MOSI/ADC3/P1.3_2") (pintype "passive"))
    )
    (net (code "153") (name "unconnected-(U2-P3.2{slash}INT0-Pad11)") (class "Default")
      (node (ref "U2") (pin "11") (pinfunction "P3.2/INT0_11") (pintype "passive"))
    )
    (net (code "154") (name "unconnected-(U2-P3.3{slash}INT1-Pad12)") (class "Default")
      (node (ref "U2") (pin "12") (pinfunction "P3.3/INT1_12") (pintype "passive"))
    )
    (net (code "155") (name "unconnected-(U2-P5.5-Pad7)") (class "Default")
      (node (ref "U2") (pin "7") (pinfunction "P5.5_7") (pintype "passive"))
    )
    (net (code "156") (name "unconnected-(U2-SCLK{slash}ADC5{slash}P1.5-Pad4)") (class "Default")
      (node (ref "U2") (pin "4") (pinfunction "SCLK/ADC5/P1.5_4") (pintype "passive"))
    )
    (net (code "157") (name "unconnected-(U2-SS{slash}ADC2{slash}P1.2-Pad1)") (class "Default")
      (node (ref "U2") (pin "1") (pinfunction "SS/ADC2/P1.2_1") (pintype "passive"))
    )
  )
)
